# main.net
KiCad netlist of a schematic drawn in Altium Designer
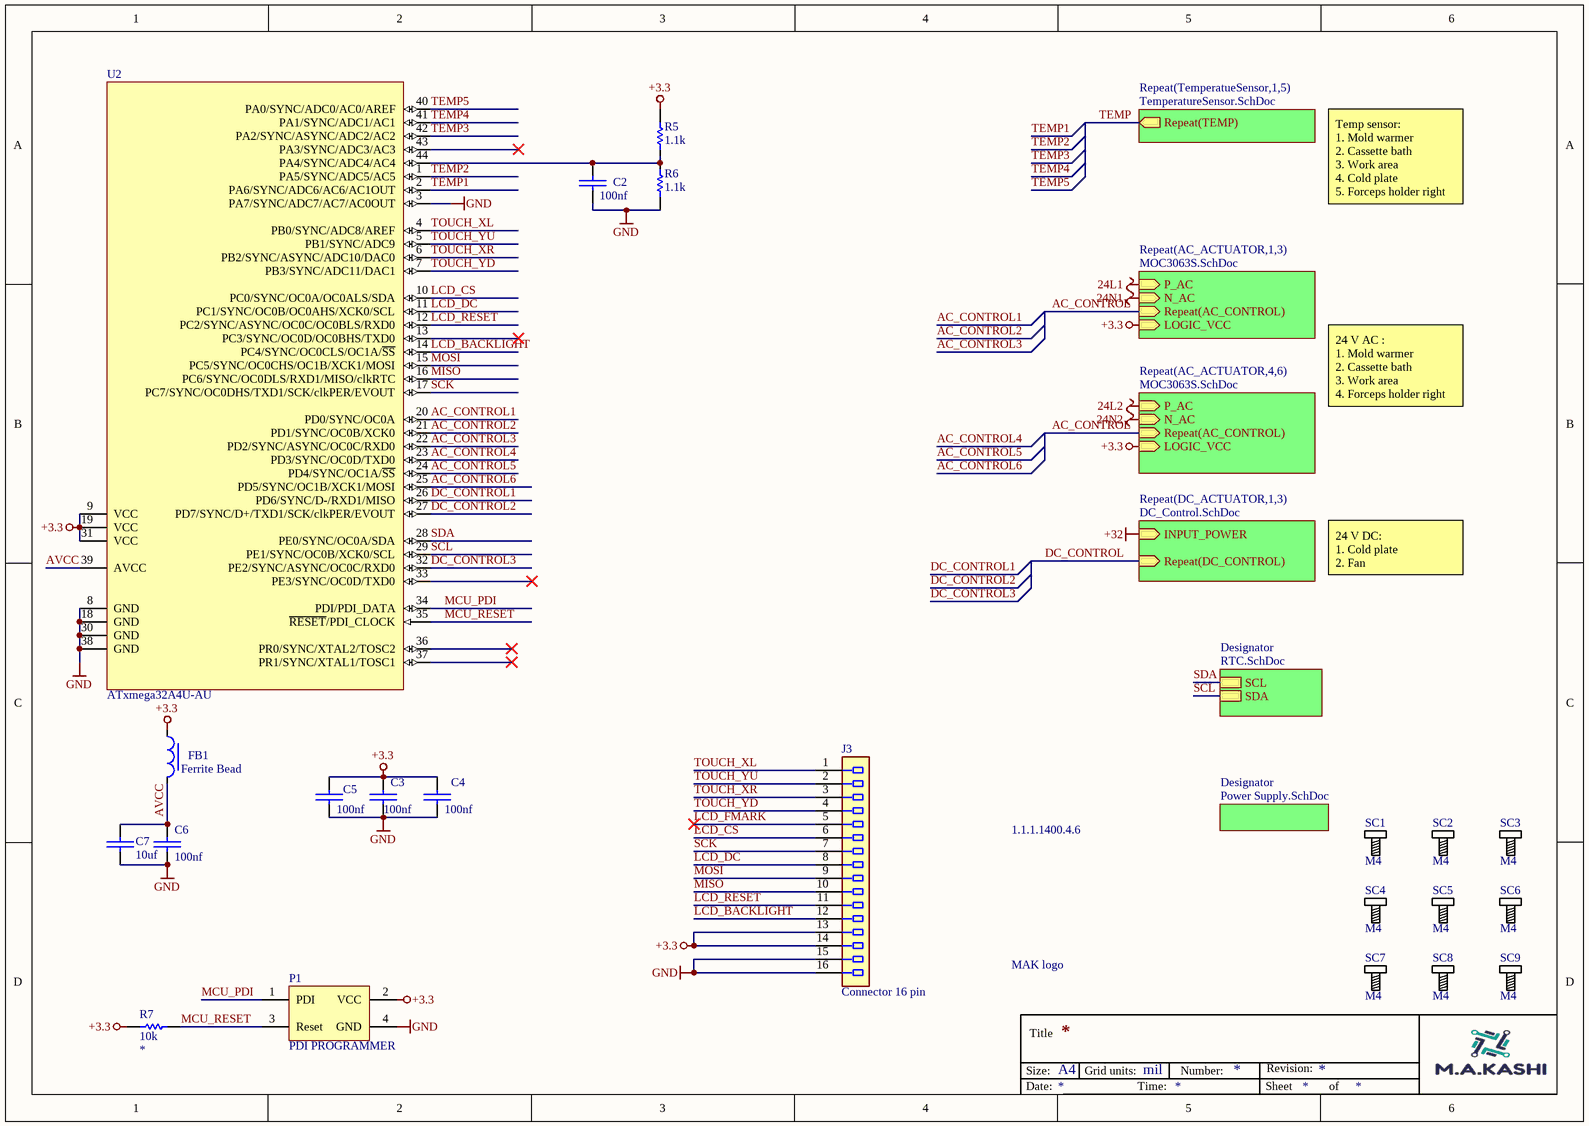
[diagram p0: main.SchDoc]

(export (version "E")
  (design (tool "Eeschema 10.0.6"))
  (components
    (comp (ref "1.1.1.1400.4.6")
      (value "MAK logo")
      (footprint "MAk LOGO")
      (libsource (lib "E-component") (part "MAK logo"))
    )
    (comp (ref "C2")
      (value "100nf")
      (footprint "cap_0805_A")
      (description "octopart or digikey description!")
      (libsource (lib "E-component") (part "Capacitor"))
    )
    (comp (ref "C3")
      (value "100nf")
      (footprint "cap_0805_A")
      (description "octopart or digikey description!")
      (libsource (lib "E-component") (part "Capacitor"))
    )
    (comp (ref "C4")
      (value "100nf")
      (footprint "cap_0805_A")
      (description "octopart or digikey description!")
      (libsource (lib "E-component") (part "Capacitor"))
    )
    (comp (ref "C5")
      (value "100nf")
      (footprint "cap_0805_A")
      (description "octopart or digikey description!")
      (libsource (lib "E-component") (part "Capacitor"))
    )
    (comp (ref "C6")
      (value "100nf")
      (footprint "cap_0805_A")
      (description "octopart or digikey description!")
      (libsource (lib "E-component") (part "Capacitor"))
    )
    (comp (ref "C7")
      (value "10uf")
      (footprint "cap_0805_A")
      (description "octopart or digikey description!")
      (libsource (lib "E-component") (part "Capacitor"))
    )
    (comp (ref "FB1")
      (value "Ferrite Bead")
      (footprint "FER_0805_A")
      (description "octopart or digikey description!")
      (libsource (lib "E-component") (part "Ferrite Bead"))
    )
    (comp (ref "J3")
      (value "Connector 16 pin")
      (footprint "DS1013-16S - with Latch/Eject Levers")
      (libsource (lib "E-component") (part "Connector 16 pin"))
    )
    (comp (ref "P1")
      (value "PDI PROGRAMMER")
      (footprint "PDI")
      (description "Header, 3-Pin, Dual row")
      (fields (field (name "PUBLISHER") "Altium Limited"))
      (libsource (lib "E-component") (part "PDI PROGRAMMER"))
    )
    (comp (ref "R5")
      (value "1.1k")
      (footprint "RES_0805_A")
      (description "octopart or digikey description!")
      (fields (field (name "PART NUMBER") "RC0402JR-07100RL"))
      (libsource (lib "E-component") (part "Resistor"))
    )
    (comp (ref "R6")
      (value "1.1k")
      (footprint "RES_0805_A")
      (description "octopart or digikey description!")
      (fields (field (name "PART NUMBER") "RC0402JR-07100RL"))
      (libsource (lib "E-component") (part "Resistor"))
    )
    (comp (ref "R7")
      (value "10k")
      (footprint "RES_0805_A")
      (description "octopart or digikey description!")
      (fields (field (name "TOLERANCE") "*"))
      (libsource (lib "E-component") (part "Resistor"))
    )
    (comp (ref "SC1")
      (value "M4")
      (footprint "SCREW_M4")
      (description "Screw")
      (libsource (lib "E-component") (part "Screw_M4"))
    )
    (comp (ref "SC2")
      (value "M4")
      (footprint "SCREW_M4")
      (description "Screw")
      (libsource (lib "E-component") (part "Screw_M4"))
    )
    (comp (ref "SC3")
      (value "M4")
      (footprint "SCREW_M4")
      (description "Screw")
      (libsource (lib "E-component") (part "Screw_M4"))
    )
    (comp (ref "SC4")
      (value "M4")
      (footprint "SCREW_M4")
      (description "Screw")
      (libsource (lib "E-component") (part "Screw_M4"))
    )
    (comp (ref "SC5")
      (value "M4")
      (footprint "SCREW_M4")
      (description "Screw")
      (libsource (lib "E-component") (part "Screw_M4"))
    )
    (comp (ref "SC6")
      (value "M4")
      (footprint "SCREW_M4")
      (description "Screw")
      (libsource (lib "E-component") (part "Screw_M4"))
    )
    (comp (ref "SC7")
      (value "M4")
      (footprint "SCREW_M4")
      (description "Screw")
      (libsource (lib "E-component") (part "Screw_M4"))
    )
    (comp (ref "SC8")
      (value "M4")
      (footprint "SCREW_M4")
      (description "Screw")
      (libsource (lib "E-component") (part "Screw_M4"))
    )
    (comp (ref "SC9")
      (value "M4")
      (footprint "SCREW_M4")
      (description "Screw")
      (libsource (lib "E-component") (part "Screw_M4"))
    )
    (comp (ref "U2")
      (value "ATxmega32A4U-AU")
      (footprint "44A_L")
      (libsource (lib "E-component") (part "ATxmega32A4U-AU"))
    )
  )
  (nets
    (net (code "1") (name "+3.3") (class "Default")
      (node (ref "C3") (pin "1") (pinfunction "1_1") (pintype "passive"))
      (node (ref "C4") (pin "1") (pinfunction "1_1") (pintype "passive"))
      (node (ref "C5") (pin "1") (pinfunction "1_1") (pintype "passive"))
      (node (ref "FB1") (pin "1") (pinfunction "1_1") (pintype "passive"))
      (node (ref "J3") (pin "13") (pinfunction "13_13") (pintype "passive"))
      (node (ref "J3") (pin "14") (pinfunction "14_14") (pintype "passive"))
      (node (ref "P1") (pin "2") (pinfunction "VCC_2") (pintype "passive"))
      (node (ref "R5") (pin "2") (pinfunction "2_2") (pintype "passive"))
      (node (ref "R7") (pin "1") (pinfunction "1_1") (pintype "passive"))
      (node (ref "U2") (pin "19") (pinfunction "VCC_19") (pintype "power_in"))
      (node (ref "U2") (pin "31") (pinfunction "VCC_31") (pintype "power_in"))
      (node (ref "U2") (pin "9") (pinfunction "VCC_9") (pintype "power_in"))
    )
    (net (code "4") (name "/AC_CONTROL1") (class "Default")
      (node (ref "U2") (pin "20") (pinfunction "PD0/SYNC/OC0A_20") (pintype "bidirectional"))
    )
    (net (code "5") (name "/AC_CONTROL2") (class "Default")
      (node (ref "U2") (pin "21") (pinfunction "PD1/SYNC/OC0B/XCK0_21") (pintype "bidirectional"))
    )
    (net (code "6") (name "/AC_CONTROL3") (class "Default")
      (node (ref "U2") (pin "22") (pinfunction "PD2/SYNC/ASYNC/OC0C/RXD0_22") (pintype "bidirectional"))
    )
    (net (code "7") (name "/AC_CONTROL4") (class "Default")
      (node (ref "U2") (pin "23") (pinfunction "PD3/SYNC/OC0D/TXD0_23") (pintype "bidirectional"))
    )
    (net (code "8") (name "/AC_CONTROL5") (class "Default")
      (node (ref "U2") (pin "24") (pinfunction "PD4/SYNC/OC1A/~{SS}_24") (pintype "bidirectional"))
    )
    (net (code "9") (name "/AC_CONTROL6") (class "Default")
      (node (ref "U2") (pin "25") (pinfunction "PD5/SYNC/OC1B/XCK1/MOSI_25") (pintype "bidirectional"))
    )
    (net (code "10") (name "/AVCC") (class "Default")
      (node (ref "C6") (pin "1") (pinfunction "1_1") (pintype "passive"))
      (node (ref "C7") (pin "1") (pinfunction "1_1") (pintype "passive"))
      (node (ref "FB1") (pin "2") (pinfunction "2_2") (pintype "passive"))
      (node (ref "U2") (pin "39") (pinfunction "AVCC_39") (pintype "power_in"))
    )
    (net (code "12") (name "/DC_CONTROL1") (class "Default")
      (node (ref "U2") (pin "26") (pinfunction "PD6/SYNC/D-/RXD1/MISO_26") (pintype "bidirectional"))
    )
    (net (code "13") (name "/DC_CONTROL2") (class "Default")
      (node (ref "U2") (pin "27") (pinfunction "PD7/SYNC/D+/TXD1/SCK/clkPER/EVOUT_27") (pintype "bidirectional"))
    )
    (net (code "14") (name "/DC_CONTROL3") (class "Default")
      (node (ref "U2") (pin "32") (pinfunction "PE2/SYNC/ASYNC/OC0C/RXD0_32") (pintype "bidirectional"))
    )
    (net (code "15") (name "/LCD_BACKLIGHT") (class "Default")
      (node (ref "J3") (pin "12") (pinfunction "12_12") (pintype "passive"))
      (node (ref "U2") (pin "14") (pinfunction "PC4/SYNC/OC0CLS/OC1A/~{SS}_14") (pintype "bidirectional"))
    )
    (net (code "16") (name "/LCD_CS") (class "Default")
      (node (ref "J3") (pin "6") (pinfunction "6_6") (pintype "passive"))
      (node (ref "U2") (pin "10") (pinfunction "PC0/SYNC/OC0A/OC0ALS/SDA_10") (pintype "bidirectional"))
    )
    (net (code "17") (name "/LCD_DC") (class "Default")
      (node (ref "J3") (pin "8") (pinfunction "8_8") (pintype "passive"))
      (node (ref "U2") (pin "11") (pinfunction "PC1/SYNC/OC0B/OC0AHS/XCK0/SCL_11") (pintype "bidirectional"))
    )
    (net (code "18") (name "/LCD_FMARK") (class "Default")
      (node (ref "J3") (pin "5") (pinfunction "5_5") (pintype "passive+no_connect"))
    )
    (net (code "19") (name "/LCD_RESET") (class "Default")
      (node (ref "J3") (pin "11") (pinfunction "11_11") (pintype "passive"))
      (node (ref "U2") (pin "12") (pinfunction "PC2/SYNC/ASYNC/OC0C/OC0BLS/RXD0_12") (pintype "bidirectional"))
    )
    (net (code "20") (name "/MCU_PDI") (class "Default")
      (node (ref "P1") (pin "1") (pinfunction "PDI_1") (pintype "passive"))
      (node (ref "U2") (pin "34") (pinfunction "PDI/PDI_DATA_34") (pintype "bidirectional"))
    )
    (net (code "21") (name "/MCU_RESET") (class "Default")
      (node (ref "P1") (pin "3") (pinfunction "Reset_3") (pintype "passive"))
      (node (ref "R7") (pin "2") (pinfunction "2_2") (pintype "passive"))
      (node (ref "U2") (pin "35") (pinfunction "~{RESET}/PDI_CLOCK_35") (pintype "input"))
    )
    (net (code "22") (name "/MISO") (class "Default")
      (node (ref "J3") (pin "10") (pinfunction "10_10") (pintype "passive"))
      (node (ref "U2") (pin "16") (pinfunction "PC6/SYNC/OC0DLS/RXD1/MISO/clkRTC_16") (pintype "bidirectional"))
    )
    (net (code "23") (name "/MOSI") (class "Default")
      (node (ref "J3") (pin "9") (pinfunction "9_9") (pintype "passive"))
      (node (ref "U2") (pin "15") (pinfunction "PC5/SYNC/OC0CHS/OC1B/XCK1/MOSI_15") (pintype "bidirectional"))
    )
    (net (code "24") (name "/SCK") (class "Default")
      (node (ref "J3") (pin "7") (pinfunction "7_7") (pintype "passive"))
      (node (ref "U2") (pin "17") (pinfunction "PC7/SYNC/OC0DHS/TXD1/SCK/clkPER/EVOUT_17") (pintype "bidirectional"))
    )
    (net (code "25") (name "/SCL") (class "Default")
      (node (ref "U2") (pin "29") (pinfunction "PE1/SYNC/OC0B/XCK0/SCL_29") (pintype "bidirectional"))
    )
    (net (code "26") (name "/SDA") (class "Default")
      (node (ref "U2") (pin "28") (pinfunction "PE0/SYNC/OC0A/SDA_28") (pintype "bidirectional"))
    )
    (net (code "28") (name "/TEMP1") (class "Default")
      (node (ref "U2") (pin "2") (pinfunction "PA6/SYNC/ADC6/AC6/AC1OUT_2") (pintype "bidirectional"))
    )
    (net (code "29") (name "/TEMP2") (class "Default")
      (node (ref "U2") (pin "1") (pinfunction "PA5/SYNC/ADC5/AC5_1") (pintype "bidirectional"))
    )
    (net (code "30") (name "/TEMP3") (class "Default")
      (node (ref "U2") (pin "42") (pinfunction "PA2/SYNC/ASYNC/ADC2/AC2_42") (pintype "bidirectional"))
    )
    (net (code "31") (name "/TEMP4") (class "Default")
      (node (ref "U2") (pin "41") (pinfunction "PA1/SYNC/ADC1/AC1_41") (pintype "bidirectional"))
    )
    (net (code "32") (name "/TEMP5") (class "Default")
      (node (ref "U2") (pin "40") (pinfunction "PA0/SYNC/ADC0/AC0/AREF_40") (pintype "bidirectional"))
    )
    (net (code "33") (name "/TOUCH_XL") (class "Default")
      (node (ref "J3") (pin "1") (pinfunction "1_1") (pintype "passive"))
      (node (ref "U2") (pin "4") (pinfunction "PB0/SYNC/ADC8/AREF_4") (pintype "bidirectional"))
    )
    (net (code "34") (name "/TOUCH_XR") (class "Default")
      (node (ref "J3") (pin "3") (pinfunction "3_3") (pintype "passive"))
      (node (ref "U2") (pin "6") (pinfunction "PB2/SYNC/ASYNC/ADC10/DAC0_6") (pintype "bidirectional"))
    )
    (net (code "35") (name "/TOUCH_YD") (class "Default")
      (node (ref "J3") (pin "4") (pinfunction "4_4") (pintype "passive"))
      (node (ref "U2") (pin "7") (pinfunction "PB3/SYNC/ADC11/DAC1_7") (pintype "bidirectional"))
    )
    (net (code "36") (name "/TOUCH_YU") (class "Default")
      (node (ref "J3") (pin "2") (pinfunction "2_2") (pintype "passive"))
      (node (ref "U2") (pin "5") (pinfunction "PB1/SYNC/ADC9_5") (pintype "bidirectional"))
    )
    (net (code "41") (name "GND") (class "Default")
      (node (ref "C2") (pin "2") (pinfunction "2_2") (pintype "passive"))
      (node (ref "C3") (pin "2") (pinfunction "2_2") (pintype "passive"))
      (node (ref "C4") (pin "2") (pinfunction "2_2") (pintype "passive"))
      (node (ref "C5") (pin "2") (pinfunction "2_2") (pintype "passive"))
      (node (ref "C6") (pin "2") (pinfunction "2_2") (pintype "passive"))
      (node (ref "C7") (pin "2") (pinfunction "2_2") (pintype "passive"))
      (node (ref "J3") (pin "15") (pinfunction "15_15") (pintype "passive"))
      (node (ref "J3") (pin "16") (pinfunction "16_16") (pintype "passive"))
      (node (ref "P1") (pin "4") (pinfunction "GND_4") (pintype "passive"))
      (node (ref "R6") (pin "1") (pinfunction "1_1") (pintype "passive"))
      (node (ref "U2") (pin "18") (pinfunction "GND_18") (pintype "power_in"))
      (node (ref "U2") (pin "3") (pinfunction "PA7/SYNC/ADC7/AC7/AC0OUT_3") (pintype "bidirectional"))
      (node (ref "U2") (pin "30") (pinfunction "GND_30") (pintype "power_in"))
      (node (ref "U2") (pin "38") (pinfunction "GND_38") (pintype "power_in"))
      (node (ref "U2") (pin "8") (pinfunction "GND_8") (pintype "power_in"))
    )
    (net (code "42") (name "Net-(U2-PA4{slash}SYNC{slash}ADC4{slash}AC4)") (class "Default")
      (node (ref "C2") (pin "1") (pinfunction "1_1") (pintype "passive"))
      (node (ref "R5") (pin "1") (pinfunction "1_1") (pintype "passive"))
      (node (ref "R6") (pin "2") (pinfunction "2_2") (pintype "passive"))
      (node (ref "U2") (pin "44") (pinfunction "PA4/SYNC/ADC4/AC4_44") (pintype "bidirectional"))
    )
    (net (code "43") (name "unconnected-(U2-PA3{slash}SYNC{slash}ADC3{slash}AC3-Pad43)") (class "Default")
      (node (ref "U2") (pin "43") (pinfunction "PA3/SYNC/ADC3/AC3_43") (pintype "bidirectional+no_connect"))
    )
    (net (code "44") (name "unconnected-(U2-PC3{slash}SYNC{slash}OC0D{slash}OC0BHS{slash}TXD0-Pad13)") (class "Default")
      (node (ref "U2") (pin "13") (pinfunction "PC3/SYNC/OC0D/OC0BHS/TXD0_13") (pintype "bidirectional+no_connect"))
    )
    (net (code "45") (name "unconnected-(U2-PE3{slash}SYNC{slash}OC0D{slash}TXD0-Pad33)") (class "Default")
      (node (ref "U2") (pin "33") (pinfunction "PE3/SYNC/OC0D/TXD0_33") (pintype "bidirectional+no_connect"))
    )
    (net (code "46") (name "unconnected-(U2-PR0{slash}SYNC{slash}XTAL2{slash}TOSC2-Pad36)") (class "Default")
      (node (ref "U2") (pin "36") (pinfunction "PR0/SYNC/XTAL2/TOSC2_36") (pintype "bidirectional+no_connect"))
    )
    (net (code "47") (name "unconnected-(U2-PR1{slash}SYNC{slash}XTAL1{slash}TOSC1-Pad37)") (class "Default")
      (node (ref "U2") (pin "37") (pinfunction "PR1/SYNC/XTAL1/TOSC1_37") (pintype "bidirectional+no_connect"))
    )
  )
)
